# control_unit.net
KiCad netlist of a schematic drawn in Altium Designer
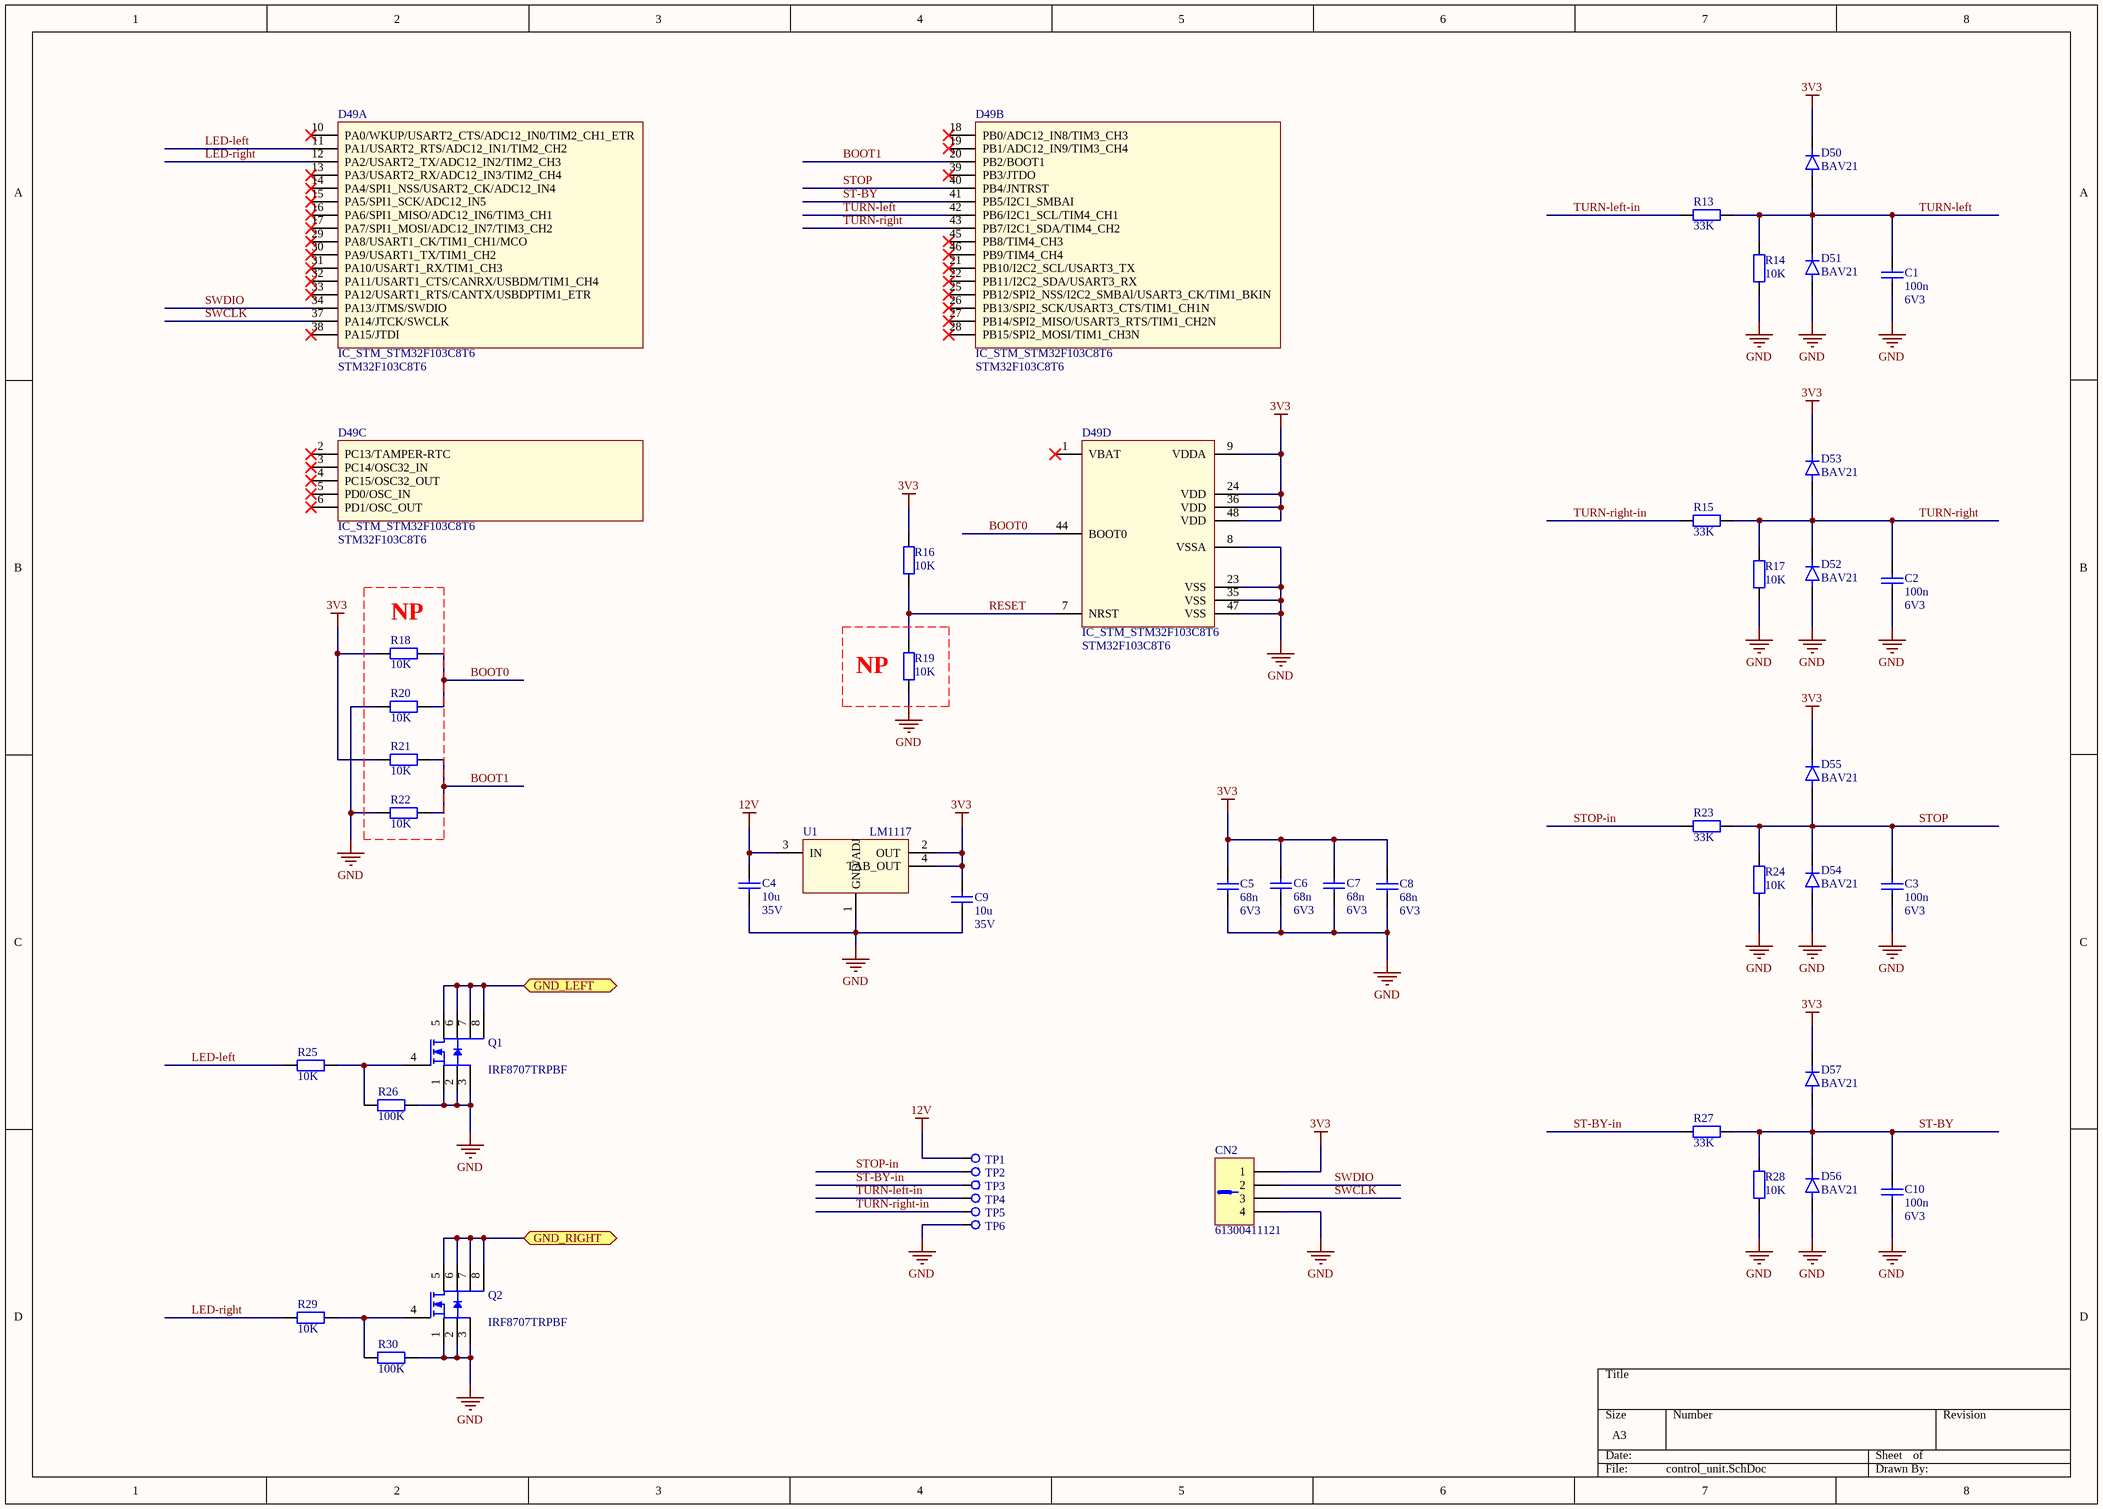
[diagram p0: control_unit.SchDoc]

(export (version "E")
  (design (tool "Eeschema 10.0.6"))
  (components
    (comp (ref "C1")
      (value "CAP")
      (footprint "CAPC2012X88N")
      (description "X7R 10% 0805")
      (fields
        (field (name "VALUE1") "100n")
        (field (name "VALUE2") "6V3")
        (field (name "MANUFACTURER") "KEMET")
      )
      (libsource (lib "DSW_Lib") (part "CAP"))
    )
    (comp (ref "C2")
      (value "CAP")
      (footprint "CAPC2012X88N")
      (description "X7R 10% 0805")
      (fields
        (field (name "VALUE1") "100n")
        (field (name "VALUE2") "6V3")
        (field (name "MANUFACTURER") "KEMET")
      )
      (libsource (lib "DSW_Lib") (part "CAP"))
    )
    (comp (ref "C3")
      (value "CAP")
      (footprint "CAPC2012X88N")
      (description "X7R 10% 0805")
      (fields
        (field (name "VALUE1") "100n")
        (field (name "VALUE2") "6V3")
        (field (name "MANUFACTURER") "KEMET")
      )
      (libsource (lib "DSW_Lib") (part "CAP"))
    )
    (comp (ref "C4")
      (value "CAP")
      (footprint "CAPC3216X18N")
      (description "MURATA - GRM31CR6YA106KA12L - CAP, MLCC, X5R, 10UF, 35V, 1206")
      (fields
        (field (name "VALUE1") "10u")
        (field (name "VALUE2") "35V")
        (field (name "MANUFACTURER") "Murata")
      )
      (libsource (lib "DSW_Lib") (part "CAP"))
    )
    (comp (ref "C5")
      (value "CAP")
      (footprint "CAPC2012X100N")
      (description "X7R 10% 0805")
      (fields
        (field (name "VALUE1") "68n")
        (field (name "VALUE2") "6V3")
        (field (name "MANUFACTURER") "KEMET")
      )
      (libsource (lib "DSW_Lib") (part "CAP"))
    )
    (comp (ref "C6")
      (value "CAP")
      (footprint "CAPC2012X100N")
      (description "X7R 10% 0805")
      (fields
        (field (name "VALUE1") "68n")
        (field (name "VALUE2") "6V3")
        (field (name "MANUFACTURER") "KEMET")
      )
      (libsource (lib "DSW_Lib") (part "CAP"))
    )
    (comp (ref "C7")
      (value "CAP")
      (footprint "CAPC2012X100N")
      (description "X7R 10% 0805")
      (fields
        (field (name "VALUE1") "68n")
        (field (name "VALUE2") "6V3")
        (field (name "MANUFACTURER") "KEMET")
      )
      (libsource (lib "DSW_Lib") (part "CAP"))
    )
    (comp (ref "C8")
      (value "CAP")
      (footprint "CAPC2012X100N")
      (description "X7R 10% 0805")
      (fields
        (field (name "VALUE1") "68n")
        (field (name "VALUE2") "6V3")
        (field (name "MANUFACTURER") "KEMET")
      )
      (libsource (lib "DSW_Lib") (part "CAP"))
    )
    (comp (ref "C9")
      (value "CAP")
      (footprint "CAPC3216X18N")
      (description "MURATA - GRM31CR6YA106KA12L - CAP, MLCC, X5R, 10UF, 35V, 1206")
      (fields
        (field (name "VALUE1") "10u")
        (field (name "VALUE2") "35V")
        (field (name "MANUFACTURER") "Murata")
      )
      (libsource (lib "DSW_Lib") (part "CAP"))
    )
    (comp (ref "C10")
      (value "CAP")
      (footprint "CAPC2012X88N")
      (description "X7R 10% 0805")
      (fields
        (field (name "VALUE1") "100n")
        (field (name "VALUE2") "6V3")
        (field (name "MANUFACTURER") "KEMET")
      )
      (libsource (lib "DSW_Lib") (part "CAP"))
    )
    (comp (ref "CN2")
      (value "CN_1X4M")
      (footprint "CN_WURTH_61300411121")
      (description "4 pin male pin header, pitch 2.54mm")
      (fields (field (name "VALUE1") "61300411121") (field (name "MANUFACTURER") "Wurth Electronics"))
      (libsource (lib "DSW_Lib") (part "CN_1X4M"))
    )
    (comp (ref "D49")
      (value "IC_STM_STM32F103C8T6")
      (footprint "TSQFP50P900X900X160-48N")
      (description "MCU 32BIT Cortex M3 64KB 20KB RAM 2X12 ADC")
      (fields (field (name "VALUE1") "STM32F103C8T6") (field (name "MANUFACTURER") "STM"))
      (libsource (lib "DSW_Lib") (part "IC_STM_STM32F103C8T6"))
    )
    (comp (ref "D50")
      (value "DIO")
      (footprint "SODFL370X136-2M")
      (description "Diodes - General Purpose, Power, Switching 250V 625mA 1A IFSM")
      (fields (field (name "VALUE1") "BAV21") (field (name "MANUFACTURER") "Vishay"))
      (libsource (lib "DSW_Lib") (part "DIO"))
    )
    (comp (ref "D51")
      (value "DIO")
      (footprint "SODFL370X136-2M")
      (description "Diodes - General Purpose, Power, Switching 250V 625mA 1A IFSM")
      (fields (field (name "VALUE1") "BAV21") (field (name "MANUFACTURER") "Vishay"))
      (libsource (lib "DSW_Lib") (part "DIO"))
    )
    (comp (ref "D52")
      (value "DIO")
      (footprint "SODFL370X136-2M")
      (description "Diodes - General Purpose, Power, Switching 250V 625mA 1A IFSM")
      (fields (field (name "VALUE1") "BAV21") (field (name "MANUFACTURER") "Vishay"))
      (libsource (lib "DSW_Lib") (part "DIO"))
    )
    (comp (ref "D53")
      (value "DIO")
      (footprint "SODFL370X136-2M")
      (description "Diodes - General Purpose, Power, Switching 250V 625mA 1A IFSM")
      (fields (field (name "VALUE1") "BAV21") (field (name "MANUFACTURER") "Vishay"))
      (libsource (lib "DSW_Lib") (part "DIO"))
    )
    (comp (ref "D54")
      (value "DIO")
      (footprint "SODFL370X136-2M")
      (description "Diodes - General Purpose, Power, Switching 250V 625mA 1A IFSM")
      (fields (field (name "VALUE1") "BAV21") (field (name "MANUFACTURER") "Vishay"))
      (libsource (lib "DSW_Lib") (part "DIO"))
    )
    (comp (ref "D55")
      (value "DIO")
      (footprint "SODFL370X136-2M")
      (description "Diodes - General Purpose, Power, Switching 250V 625mA 1A IFSM")
      (fields (field (name "VALUE1") "BAV21") (field (name "MANUFACTURER") "Vishay"))
      (libsource (lib "DSW_Lib") (part "DIO"))
    )
    (comp (ref "D56")
      (value "DIO")
      (footprint "SODFL370X136-2M")
      (description "Diodes - General Purpose, Power, Switching 250V 625mA 1A IFSM")
      (fields (field (name "VALUE1") "BAV21") (field (name "MANUFACTURER") "Vishay"))
      (libsource (lib "DSW_Lib") (part "DIO"))
    )
    (comp (ref "D57")
      (value "DIO")
      (footprint "SODFL370X136-2M")
      (description "Diodes - General Purpose, Power, Switching 250V 625mA 1A IFSM")
      (fields (field (name "VALUE1") "BAV21") (field (name "MANUFACTURER") "Vishay"))
      (libsource (lib "DSW_Lib") (part "DIO"))
    )
    (comp (ref "Q1")
      (value "TRS_INFINEON_IRF8707TRPBF")
      (footprint "SOIC127P600X175-8N")
      (description "MOSFET MOSFT 30V 11A 11.9mOhm 6.2nC Qg")
      (fields (field (name "VALUE1") "IRF8707TRPBF") (field (name "MANUFACTURER") "Infineon"))
      (libsource (lib "DSW_Lib") (part "TRS_INFINEON_IRF8707TRPBF"))
    )
    (comp (ref "Q2")
      (value "TRS_INFINEON_IRF8707TRPBF")
      (footprint "SOIC127P600X175-8N")
      (description "MOSFET MOSFT 30V 11A 11.9mOhm 6.2nC Qg")
      (fields (field (name "VALUE1") "IRF8707TRPBF") (field (name "MANUFACTURER") "Infineon"))
      (libsource (lib "DSW_Lib") (part "TRS_INFINEON_IRF8707TRPBF"))
    )
    (comp (ref "R13")
      (value "RES")
      (footprint "RESC2012X60N")
      (description "RESISTOR, 0805, 33K, 1%, SMD")
      (fields (field (name "VALUE1") "33K") (field (name "MANUFACTURER") "Yageo"))
      (libsource (lib "") (part "RES_1"))
    )
    (comp (ref "R14")
      (value "RES")
      (footprint "RESC2012X60N")
      (description "RESISTOR, 0805, 10K, 1%, SMD")
      (fields (field (name "VALUE1") "10K") (field (name "MANUFACTURER") "Yageo"))
      (libsource (lib "DSW_Lib") (part "RES"))
    )
    (comp (ref "R15")
      (value "RES")
      (footprint "RESC2012X60N")
      (description "RESISTOR, 0805, 33K, 1%, SMD")
      (fields (field (name "VALUE1") "33K") (field (name "MANUFACTURER") "Yageo"))
      (libsource (lib "") (part "RES_1"))
    )
    (comp (ref "R16")
      (value "RES")
      (footprint "RESC2012X60N")
      (description "RESISTOR, 0805, 10K, 1%, SMD")
      (fields (field (name "VALUE1") "10K") (field (name "MANUFACTURER") "Yageo"))
      (libsource (lib "DSW_Lib") (part "RES"))
    )
    (comp (ref "R17")
      (value "RES")
      (footprint "RESC2012X60N")
      (description "RESISTOR, 0805, 10K, 1%, SMD")
      (fields (field (name "VALUE1") "10K") (field (name "MANUFACTURER") "Yageo"))
      (libsource (lib "") (part "RES_3"))
    )
    (comp (ref "R18")
      (value "RES")
      (footprint "RESC2012X60N")
      (description "RESISTOR, 0805, 10K, 1%, SMD")
      (fields (field (name "VALUE1") "10K") (field (name "MANUFACTURER") "Yageo"))
      (libsource (lib "") (part "RES_1"))
    )
    (comp (ref "R19")
      (value "RES")
      (footprint "RESC2012X60N")
      (description "RESISTOR, 0805, 10K, 1%, SMD")
      (fields (field (name "VALUE1") "10K") (field (name "MANUFACTURER") "Yageo"))
      (libsource (lib "DSW_Lib") (part "RES"))
    )
    (comp (ref "R20")
      (value "RES")
      (footprint "RESC2012X60N")
      (description "RESISTOR, 0805, 10K, 1%, SMD")
      (fields (field (name "VALUE1") "10K") (field (name "MANUFACTURER") "Yageo"))
      (libsource (lib "") (part "RES_1"))
    )
    (comp (ref "R21")
      (value "RES")
      (footprint "RESC2012X60N")
      (description "RESISTOR, 0805, 10K, 1%, SMD")
      (fields (field (name "VALUE1") "10K") (field (name "MANUFACTURER") "Yageo"))
      (libsource (lib "") (part "RES_1"))
    )
    (comp (ref "R22")
      (value "RES")
      (footprint "RESC2012X60N")
      (description "RESISTOR, 0805, 10K, 1%, SMD")
      (fields (field (name "VALUE1") "10K") (field (name "MANUFACTURER") "Yageo"))
      (libsource (lib "") (part "RES_1"))
    )
    (comp (ref "R23")
      (value "RES")
      (footprint "RESC2012X60N")
      (description "RESISTOR, 0805, 33K, 1%, SMD")
      (fields (field (name "VALUE1") "33K") (field (name "MANUFACTURER") "Yageo"))
      (libsource (lib "") (part "RES_1"))
    )
    (comp (ref "R24")
      (value "RES")
      (footprint "RESC2012X60N")
      (description "RESISTOR, 0805, 10K, 1%, SMD")
      (fields (field (name "VALUE1") "10K") (field (name "MANUFACTURER") "Yageo"))
      (libsource (lib "") (part "RES_3"))
    )
    (comp (ref "R25")
      (value "RES")
      (footprint "RESC2012X60N")
      (description "RESISTOR, 0805, 10K, 1%, SMD")
      (fields (field (name "VALUE1") "10K") (field (name "MANUFACTURER") "Yageo"))
      (libsource (lib "") (part "RES_2"))
    )
    (comp (ref "R26")
      (value "RES")
      (footprint "RESC2012X60N")
      (description "RESISTOR, 0805, 100K, 1%, SMD")
      (fields (field (name "VALUE1") "100K") (field (name "MANUFACTURER") "Yageo"))
      (libsource (lib "") (part "RES_1"))
    )
    (comp (ref "R27")
      (value "RES")
      (footprint "RESC2012X60N")
      (description "RESISTOR, 0805, 33K, 1%, SMD")
      (fields (field (name "VALUE1") "33K") (field (name "MANUFACTURER") "Yageo"))
      (libsource (lib "") (part "RES_1"))
    )
    (comp (ref "R28")
      (value "RES")
      (footprint "RESC2012X60N")
      (description "RESISTOR, 0805, 10K, 1%, SMD")
      (fields (field (name "VALUE1") "10K") (field (name "MANUFACTURER") "Yageo"))
      (libsource (lib "DSW_Lib") (part "RES"))
    )
    (comp (ref "R29")
      (value "RES")
      (footprint "RESC2012X60N")
      (description "RESISTOR, 0805, 10K, 1%, SMD")
      (fields (field (name "VALUE1") "10K") (field (name "MANUFACTURER") "Yageo"))
      (libsource (lib "") (part "RES_2"))
    )
    (comp (ref "R30")
      (value "RES")
      (footprint "RESC2012X60N")
      (description "RESISTOR, 0805, 100K, 1%, SMD")
      (fields (field (name "VALUE1") "100K") (field (name "MANUFACTURER") "Yageo"))
      (libsource (lib "") (part "RES_1"))
    )
    (comp (ref "TP1")
      (value "MSC_TP")
      (footprint "MSC_TP_THT1MM")
      (description "With Hole for 1 header pin")
      (libsource (lib "DSW_Lib") (part "MSC_TP"))
    )
    (comp (ref "TP2")
      (value "MSC_TP")
      (footprint "MSC_TP_THT1MM")
      (description "With Hole for 1 header pin")
      (libsource (lib "DSW_Lib") (part "MSC_TP"))
    )
    (comp (ref "TP3")
      (value "MSC_TP")
      (footprint "MSC_TP_THT1MM")
      (description "With Hole for 1 header pin")
      (libsource (lib "DSW_Lib") (part "MSC_TP"))
    )
    (comp (ref "TP4")
      (value "MSC_TP")
      (footprint "MSC_TP_THT1MM")
      (description "With Hole for 1 header pin")
      (libsource (lib "DSW_Lib") (part "MSC_TP"))
    )
    (comp (ref "TP5")
      (value "MSC_TP")
      (footprint "MSC_TP_THT1MM")
      (description "With Hole for 1 header pin")
      (libsource (lib "DSW_Lib") (part "MSC_TP"))
    )
    (comp (ref "TP6")
      (value "MSC_TP")
      (footprint "MSC_TP_THT1MM")
      (description "With Hole for 1 header pin")
      (libsource (lib "DSW_Lib") (part "MSC_TP"))
    )
    (comp (ref "U1")
      (value "IC_TI_LM1117")
      (footprint "IC_TI_LM1117")
      (description "LDO Voltage Regulators 800MA LDO LINEAR REG")
      (fields (field (name "VALUE1") "LM1117") (field (name "MANUFACTURER") "TI"))
      (libsource (lib "DSW_Lib") (part "IC_TI_LM1117"))
    )
  )
  (nets
    (net (code "1") (name "/BOOT0") (class "Default")
      (node (ref "D49") (pin "44") (pinfunction "BOOT0_44") (pintype "passive"))
      (node (ref "R18") (pin "2") (pinfunction "2_2") (pintype "passive"))
      (node (ref "R20") (pin "2") (pinfunction "2_2") (pintype "passive"))
    )
    (net (code "2") (name "/BOOT1") (class "Default")
      (node (ref "D49") (pin "20") (pinfunction "PB2/BOOT1_20") (pintype "passive"))
      (node (ref "R21") (pin "2") (pinfunction "2_2") (pintype "passive"))
      (node (ref "R22") (pin "2") (pinfunction "2_2") (pintype "passive"))
    )
    (net (code "3") (name "/GND_LEFT") (class "Default")
      (node (ref "Q1") (pin "5") (pinfunction "D_5") (pintype "passive"))
      (node (ref "Q1") (pin "6") (pinfunction "D_6") (pintype "passive"))
      (node (ref "Q1") (pin "7") (pinfunction "D_7") (pintype "passive"))
      (node (ref "Q1") (pin "8") (pinfunction "D_8") (pintype "passive"))
    )
    (net (code "4") (name "/GND_RIGHT") (class "Default")
      (node (ref "Q2") (pin "5") (pinfunction "D_5") (pintype "passive"))
      (node (ref "Q2") (pin "6") (pinfunction "D_6") (pintype "passive"))
      (node (ref "Q2") (pin "7") (pinfunction "D_7") (pintype "passive"))
      (node (ref "Q2") (pin "8") (pinfunction "D_8") (pintype "passive"))
    )
    (net (code "5") (name "/LED-left") (class "Default")
      (node (ref "D49") (pin "11") (pinfunction "PA1/USART2_RTS/ADC12_IN1/TIM2_CH2_11") (pintype "passive"))
      (node (ref "R25") (pin "2") (pinfunction "2_2") (pintype "passive"))
    )
    (net (code "6") (name "/LED-right") (class "Default")
      (node (ref "D49") (pin "12") (pinfunction "PA2/USART2_TX/ADC12_IN2/TIM2_CH3_12") (pintype "passive"))
      (node (ref "R29") (pin "2") (pinfunction "2_2") (pintype "passive"))
    )
    (net (code "7") (name "/RESET") (class "Default")
      (node (ref "D49") (pin "7") (pinfunction "NRST_7") (pintype "passive"))
      (node (ref "R16") (pin "1") (pinfunction "1_1") (pintype "passive"))
      (node (ref "R19") (pin "2") (pinfunction "2_2") (pintype "passive"))
    )
    (net (code "8") (name "/ST-BY") (class "Default")
      (node (ref "C10") (pin "2") (pinfunction "2_2") (pintype "passive"))
      (node (ref "D49") (pin "41") (pinfunction "PB5/I2C1_SMBAI_41") (pintype "passive"))
      (node (ref "D56") (pin "1") (pinfunction "K_1") (pintype "passive"))
      (node (ref "D57") (pin "2") (pinfunction "A_2") (pintype "passive"))
      (node (ref "R27") (pin "2") (pinfunction "2_2") (pintype "passive"))
      (node (ref "R28") (pin "2") (pinfunction "2_2") (pintype "passive"))
    )
    (net (code "9") (name "/ST-BY-in") (class "Default")
      (node (ref "R27") (pin "1") (pinfunction "1_1") (pintype "passive"))
      (node (ref "TP3") (pin "1") (pinfunction "1_1") (pintype "passive"))
    )
    (net (code "10") (name "/STOP") (class "Default")
      (node (ref "C3") (pin "2") (pinfunction "2_2") (pintype "passive"))
      (node (ref "D49") (pin "40") (pinfunction "PB4/JNTRST_40") (pintype "passive"))
      (node (ref "D54") (pin "1") (pinfunction "K_1") (pintype "passive"))
      (node (ref "D55") (pin "2") (pinfunction "A_2") (pintype "passive"))
      (node (ref "R23") (pin "2") (pinfunction "2_2") (pintype "passive"))
      (node (ref "R24") (pin "1") (pinfunction "1_1") (pintype "passive"))
    )
    (net (code "11") (name "/STOP-in") (class "Default")
      (node (ref "R23") (pin "1") (pinfunction "1_1") (pintype "passive"))
      (node (ref "TP2") (pin "1") (pinfunction "1_1") (pintype "passive"))
    )
    (net (code "12") (name "/SWCLK") (class "Default")
      (node (ref "CN2") (pin "3") (pinfunction "3_3") (pintype "passive"))
      (node (ref "D49") (pin "37") (pinfunction "PA14/JTCK/SWCLK_37") (pintype "passive"))
    )
    (net (code "13") (name "/SWDIO") (class "Default")
      (node (ref "CN2") (pin "2") (pinfunction "2_2") (pintype "passive"))
      (node (ref "D49") (pin "34") (pinfunction "PA13_34") (pintype "passive"))
    )
    (net (code "14") (name "/TURN-left") (class "Default")
      (node (ref "C1") (pin "2") (pinfunction "2_2") (pintype "passive"))
      (node (ref "D49") (pin "42") (pinfunction "PB6/I2C1_SCL/TIM4_CH1_42") (pintype "passive"))
      (node (ref "D50") (pin "2") (pinfunction "A_2") (pintype "passive"))
      (node (ref "D51") (pin "1") (pinfunction "K_1") (pintype "passive"))
      (node (ref "R13") (pin "2") (pinfunction "2_2") (pintype "passive"))
      (node (ref "R14") (pin "2") (pinfunction "2_2") (pintype "passive"))
    )
    (net (code "15") (name "/TURN-left-in") (class "Default")
      (node (ref "R13") (pin "1") (pinfunction "1_1") (pintype "passive"))
      (node (ref "TP4") (pin "1") (pinfunction "1_1") (pintype "passive"))
    )
    (net (code "16") (name "/TURN-right") (class "Default")
      (node (ref "C2") (pin "2") (pinfunction "2_2") (pintype "passive"))
      (node (ref "D49") (pin "43") (pinfunction "PB7/I2C1_SDA/TIM4_CH2_43") (pintype "passive"))
      (node (ref "D52") (pin "1") (pinfunction "K_1") (pintype "passive"))
      (node (ref "D53") (pin "2") (pinfunction "A_2") (pintype "passive"))
      (node (ref "R15") (pin "2") (pinfunction "2_2") (pintype "passive"))
      (node (ref "R17") (pin "1") (pinfunction "1_1") (pintype "passive"))
    )
    (net (code "17") (name "/TURN-right-in") (class "Default")
      (node (ref "R15") (pin "1") (pinfunction "1_1") (pintype "passive"))
      (node (ref "TP5") (pin "1") (pinfunction "1_1") (pintype "passive"))
    )
    (net (code "18") (name "3V3") (class "Default")
      (node (ref "C5") (pin "2") (pinfunction "2_2") (pintype "passive"))
      (node (ref "C6") (pin "2") (pinfunction "2_2") (pintype "passive"))
      (node (ref "C7") (pin "2") (pinfunction "2_2") (pintype "passive"))
      (node (ref "C8") (pin "2") (pinfunction "2_2") (pintype "passive"))
      (node (ref "C9") (pin "2") (pinfunction "2_2") (pintype "passive"))
      (node (ref "CN2") (pin "1") (pinfunction "1_1") (pintype "passive"))
      (node (ref "D49") (pin "24") (pinfunction "VDD_24") (pintype "passive"))
      (node (ref "D49") (pin "36") (pinfunction "VDD_36") (pintype "passive"))
      (node (ref "D49") (pin "48") (pinfunction "VDD_48") (pintype "passive"))
      (node (ref "D49") (pin "9") (pinfunction "VDDA_9") (pintype "passive"))
      (node (ref "D50") (pin "1") (pinfunction "K_1") (pintype "passive"))
      (node (ref "D53") (pin "1") (pinfunction "K_1") (pintype "passive"))
      (node (ref "D55") (pin "1") (pinfunction "K_1") (pintype "passive"))
      (node (ref "D57") (pin "1") (pinfunction "K_1") (pintype "passive"))
      (node (ref "R16") (pin "2") (pinfunction "2_2") (pintype "passive"))
      (node (ref "R18") (pin "1") (pinfunction "1_1") (pintype "passive"))
      (node (ref "R21") (pin "1") (pinfunction "1_1") (pintype "passive"))
      (node (ref "U1") (pin "2") (pinfunction "OUT_2") (pintype "passive"))
      (node (ref "U1") (pin "4") (pinfunction "TAB_OUT_4") (pintype "passive"))
    )
    (net (code "19") (name "12V") (class "Default")
      (node (ref "C4") (pin "2") (pinfunction "2_2") (pintype "passive"))
      (node (ref "TP1") (pin "1") (pinfunction "1_1") (pintype "passive"))
      (node (ref "U1") (pin "3") (pinfunction "IN_3") (pintype "passive"))
    )
    (net (code "20") (name "GND") (class "Default")
      (node (ref "C1") (pin "1") (pinfunction "1_1") (pintype "passive"))
      (node (ref "C10") (pin "1") (pinfunction "1_1") (pintype "passive"))
      (node (ref "C2") (pin "1") (pinfunction "1_1") (pintype "passive"))
      (node (ref "C3") (pin "1") (pinfunction "1_1") (pintype "passive"))
      (node (ref "C4") (pin "1") (pinfunction "1_1") (pintype "passive"))
      (node (ref "C5") (pin "1") (pinfunction "1_1") (pintype "passive"))
      (node (ref "C6") (pin "1") (pinfunction "1_1") (pintype "passive"))
      (node (ref "C7") (pin "1") (pinfunction "1_1") (pintype "passive"))
      (node (ref "C8") (pin "1") (pinfunction "1_1") (pintype "passive"))
      (node (ref "C9") (pin "1") (pinfunction "1_1") (pintype "passive"))
      (node (ref "CN2") (pin "4") (pinfunction "4_4") (pintype "passive"))
      (node (ref "D49") (pin "23") (pinfunction "VSS_23") (pintype "passive"))
      (node (ref "D49") (pin "35") (pinfunction "VSS_35") (pintype "passive"))
      (node (ref "D49") (pin "47") (pinfunction "VSS_47") (pintype "passive"))
      (node (ref "D49") (pin "8") (pinfunction "VSSA_8") (pintype "passive"))
      (node (ref "D51") (pin "2") (pinfunction "A_2") (pintype "passive"))
      (node (ref "D52") (pin "2") (pinfunction "A_2") (pintype "passive"))
      (node (ref "D54") (pin "2") (pinfunction "A_2") (pintype "passive"))
      (node (ref "D56") (pin "2") (pinfunction "A_2") (pintype "passive"))
      (node (ref "Q1") (pin "1") (pinfunction "S_1") (pintype "passive"))
      (node (ref "Q1") (pin "2") (pinfunction "S_2") (pintype "passive"))
      (node (ref "Q1") (pin "3") (pinfunction "D_3") (pintype "passive"))
      (node (ref "Q2") (pin "1") (pinfunction "S_1") (pintype "passive"))
      (node (ref "Q2") (pin "2") (pinfunction "S_2") (pintype "passive"))
      (node (ref "Q2") (pin "3") (pinfunction "D_3") (pintype "passive"))
      (node (ref "R14") (pin "1") (pinfunction "1_1") (pintype "passive"))
      (node (ref "R17") (pin "2") (pinfunction "2_2") (pintype "passive"))
      (node (ref "R19") (pin "1") (pinfunction "1_1") (pintype "passive"))
      (node (ref "R20") (pin "1") (pinfunction "1_1") (pintype "passive"))
      (node (ref "R22") (pin "1") (pinfunction "1_1") (pintype "passive"))
      (node (ref "R24") (pin "2") (pinfunction "2_2") (pintype "passive"))
      (node (ref "R26") (pin "2") (pinfunction "2_2") (pintype "passive"))
      (node (ref "R28") (pin "1") (pinfunction "1_1") (pintype "passive"))
      (node (ref "R30") (pin "2") (pinfunction "2_2") (pintype "passive"))
      (node (ref "TP6") (pin "1") (pinfunction "1_1") (pintype "passive"))
      (node (ref "U1") (pin "1") (pinfunction "GND/ADJ_1") (pintype "passive"))
    )
    (net (code "21") (name "Net-(Q1-G)") (class "Default")
      (node (ref "Q1") (pin "4") (pinfunction "G_4") (pintype "passive"))
      (node (ref "R25") (pin "1") (pinfunction "1_1") (pintype "passive"))
      (node (ref "R26") (pin "1") (pinfunction "1_1") (pintype "passive"))
    )
    (net (code "22") (name "Net-(Q2-G)") (class "Default")
      (node (ref "Q2") (pin "4") (pinfunction "G_4") (pintype "passive"))
      (node (ref "R29") (pin "1") (pinfunction "1_1") (pintype "passive"))
      (node (ref "R30") (pin "1") (pinfunction "1_1") (pintype "passive"))
    )
    (net (code "23") (name "unconnected-(D49A-PA0{slash}WKUP{slash}USART2_CTS{slash}ADC12_IN0{slash}TIM2_CH1_ETR-Pad10)") (class "Default")
      (node (ref "D49") (pin "10") (pinfunction "PA0/WKUP/USART2_CTS/ADC12_IN0/TIM2_CH1_ETR_10") (pintype "passive+no_connect"))
    )
    (net (code "24") (name "unconnected-(D49A-PA3{slash}USART2_RX{slash}ADC12_IN3{slash}TIM2_CH4-Pad13)") (class "Default")
      (node (ref "D49") (pin "13") (pinfunction "PA3/USART2_RX/ADC12_IN3/TIM2_CH4_13") (pintype "passive+no_connect"))
    )
    (net (code "25") (name "unconnected-(D49A-PA4{slash}SPI1_NSS{slash}USART2_CK{slash}ADC12_IN4-Pad14)") (class "Default")
      (node (ref "D49") (pin "14") (pinfunction "PA4/SPI1_NSS/USART2_CK/ADC12_IN4_14") (pintype "passive+no_connect"))
    )
    (net (code "26") (name "unconnected-(D49A-PA5{slash}SPI1_SCK{slash}ADC12_IN5-Pad15)") (class "Default")
      (node (ref "D49") (pin "15") (pinfunction "PA5/SPI1_SCK/ADC12_IN5_15") (pintype "passive+no_connect"))
    )
    (net (code "27") (name "unconnected-(D49A-PA6{slash}SPI1_MISO{slash}ADC12_IN6{slash}TIM3_CH1-Pad16)") (class "Default")
      (node (ref "D49") (pin "16") (pinfunction "PA6/SPI1_MISO/ADC12_IN6/TIM3_CH1_16") (pintype "passive+no_connect"))
    )
    (net (code "28") (name "unconnected-(D49A-PA7{slash}SPI1_MOSI{slash}ADC12_IN7{slash}TIM3_CH2-Pad17)") (class "Default")
      (node (ref "D49") (pin "17") (pinfunction "PA7/SPI1_MOSI/ADC12_IN7/TIM3_CH2_17") (pintype "passive+no_connect"))
    )
    (net (code "29") (name "unconnected-(D49A-PA8{slash}USART1_CK{slash}TIM1_CH1{slash}MCO-Pad29)") (class "Default")
      (node (ref "D49") (pin "29") (pinfunction "PA8/USART1_CK/TIM1_CH1/MCO_29") (pintype "passive+no_connect"))
    )
    (net (code "30") (name "unconnected-(D49A-PA9{slash}USART1_TX{slash}TIM1_CH2-Pad30)") (class "Default")
      (node (ref "D49") (pin "30") (pinfunction "PA9/USART1_TX/TIM1_CH2_30") (pintype "passive+no_connect"))
    )
    (net (code "31") (name "unconnected-(D49A-PA10{slash}USART1_RX{slash}TIM1_CH3-Pad31)") (class "Default")
      (node (ref "D49") (pin "31") (pinfunction "PA10/USART1_RX/TIM1_CH3_31") (pintype "passive+no_connect"))
    )
    (net (code "32") (name "unconnected-(D49A-PA11{slash}USART1_CTS{slash}CANRX{slash}USBDM{slash}TIM1_CH4-Pad32)") (class "Default")
      (node (ref "D49") (pin "32") (pinfunction "PA11/USART1_CTS/CANRX/USBDM/TIM1_CH4_32") (pintype "passive+no_connect"))
    )
    (net (code "33") (name "unconnected-(D49A-PA12{slash}USART1_RTS{slash}CANTX{slash}USBDPTIM1_ETR-Pad33)") (class "Default")
      (node (ref "D49") (pin "33") (pinfunction "PA12/USART1_RTS/CANTX/USBDPTIM1_ETR_33") (pintype "passive+no_connect"))
    )
    (net (code "34") (name "unconnected-(D49A-PA15{slash}JTDI-Pad38)") (class "Default")
      (node (ref "D49") (pin "38") (pinfunction "PA15/JTDI_38") (pintype "passive+no_connect"))
    )
    (net (code "35") (name "unconnected-(D49B-PB0{slash}ADC12_IN8{slash}TIM3_CH3-Pad18)") (class "Default")
      (node (ref "D49") (pin "18") (pinfunction "PB0/ADC12_IN8/TIM3_CH3_18") (pintype "passive+no_connect"))
    )
    (net (code "36") (name "unconnected-(D49B-PB1{slash}ADC12_IN9{slash}TIM3_CH4-Pad19)") (class "Default")
      (node (ref "D49") (pin "19") (pinfunction "PB1/ADC12_IN9/TIM3_CH4_19") (pintype "passive+no_connect"))
    )
    (net (code "37") (name "unconnected-(D49B-PB3{slash}JTDO-Pad39)") (class "Default")
      (node (ref "D49") (pin "39") (pinfunction "PB3/JTDO_39") (pintype "passive+no_connect"))
    )
    (net (code "38") (name "unconnected-(D49B-PB8{slash}TIM4_CH3-Pad45)") (class "Default")
      (node (ref "D49") (pin "45") (pinfunction "PB8/TIM4_CH3_45") (pintype "passive+no_connect"))
    )
    (net (code "39") (name "unconnected-(D49B-PB9{slash}TIM4_CH4-Pad46)") (class "Default")
      (node (ref "D49") (pin "46") (pinfunction "PB9/TIM4_CH4_46") (pintype "passive+no_connect"))
    )
    (net (code "40") (name "unconnected-(D49B-PB10{slash}I2C2_SCL{slash}USART3_TX-Pad21)") (class "Default")
      (node (ref "D49") (pin "21") (pinfunction "PB10/I2C2_SCL/USART3_TX_21") (pintype "passive+no_connect"))
    )
    (net (code "41") (name "unconnected-(D49B-PB11{slash}I2C2_SDA{slash}USART3_RX-Pad22)") (class "Default")
      (node (ref "D49") (pin "22") (pinfunction "PB11/I2C2_SDA/USART3_RX_22") (pintype "passive+no_connect"))
    )
    (net (code "42") (name "unconnected-(D49B-PB12{slash}SPI2_NSS{slash}I2C2_SMBAl{slash}USART3_CK{slash}TIM1_BKIN-Pad25)") (class "Default")
      (node (ref "D49") (pin "25") (pinfunction "PB12/SPI2_NSS/I2C2_SMBAl/USART3_CK/TIM1_BKIN_25") (pintype "passive+no_connect"))
    )
    (net (code "43") (name "unconnected-(D49B-PB13{slash}SPI2_SCK{slash}USART3_CTS{slash}TIM1_CH1N-Pad26)") (class "Default")
      (node (ref "D49") (pin "26") (pinfunction "PB13/SPI2_SCK/USART3_CTS/TIM1_CH1N_26") (pintype "passive+no_connect"))
    )
    (net (code "44") (name "unconnected-(D49B-PB14{slash}SPI2_MISO{slash}USART3_RTS{slash}TIM1_CH2N-Pad27)") (class "Default")
      (node (ref "D49") (pin "27") (pinfunction "PB14/SPI2_MISO/USART3_RTS/TIM1_CH2N_27") (pintype "passive+no_connect"))
    )
    (net (code "45") (name "unconnected-(D49B-PB15{slash}SPI2_MOSI{slash}TIM1_CH3N-Pad28)") (class "Default")
      (node (ref "D49") (pin "28") (pinfunction "PB15/SPI2_MOSI/TIM1_CH3N_28") (pintype "passive+no_connect"))
    )
    (net (code "46") (name "unconnected-(D49C-PC13{slash}TAMPER-RTC-Pad2)") (class "Default")
      (node (ref "D49") (pin "2") (pinfunction "PC13/TAMPER-RTC_2") (pintype "passive+no_connect"))
    )
    (net (code "47") (name "unconnected-(D49C-PC14{slash}OSC32_IN-Pad3)") (class "Default")
      (node (ref "D49") (pin "3") (pinfunction "PC14/OSC32_IN_3") (pintype "passive+no_connect"))
    )
    (net (code "48") (name "unconnected-(D49C-PC15{slash}OSC32_OUT-Pad4)") (class "Default")
      (node (ref "D49") (pin "4") (pinfunction "PC15/OSC32_OUT_4") (pintype "passive+no_connect"))
    )
    (net (code "49") (name "unconnected-(D49C-PD0{slash}OSC_IN-Pad5)") (class "Default")
      (node (ref "D49") (pin "5") (pinfunction "PD0/OSC_IN_5") (pintype "passive+no_connect"))
    )
    (net (code "50") (name "unconnected-(D49C-PD1{slash}OSC_OUT-Pad6)") (class "Default")
      (node (ref "D49") (pin "6") (pinfunction "PD1/OSC_OUT_6") (pintype "passive+no_connect"))
    )
    (net (code "51") (name "unconnected-(D49D-VBAT-Pad1)") (class "Default")
      (node (ref "D49") (pin "1") (pinfunction "VBAT_1") (pintype "passive+no_connect"))
    )
  )
)
